# powerStage.net
KiCad netlist of a schematic drawn in EAGLE
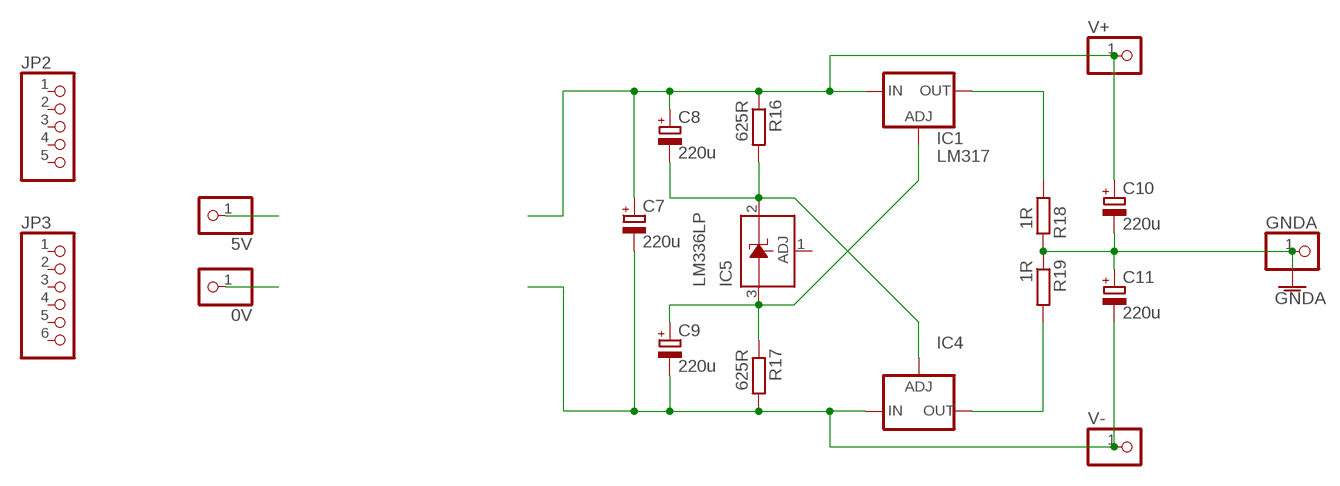
[diagram p0: schematic, sheet 1]

(export (version "E")
  (design (tool "Eeschema 10.0.6"))
  (components
    (comp (ref "0V")
      (value "PINHD-1X1")
      (footprint "eagle-import:1X01")
      (libsource (lib "eagle-import") (part "PINHD-1X1"))
    )
    (comp (ref "5V")
      (value "PINHD-1X1")
      (footprint "eagle-import:1X01")
      (libsource (lib "eagle-import") (part "PINHD-1X1"))
    )
    (comp (ref "C7")
      (value "220u")
      (footprint "eagle-import:E2-5")
      (libsource (lib "eagle-import") (part "CPOL-EUE2-5"))
    )
    (comp (ref "C8")
      (value "220u")
      (footprint "eagle-import:E2-5")
      (libsource (lib "eagle-import") (part "CPOL-EUE2-5"))
    )
    (comp (ref "C9")
      (value "220u")
      (footprint "eagle-import:E2-5")
      (libsource (lib "eagle-import") (part "CPOL-EUE2-5"))
    )
    (comp (ref "C10")
      (value "220u")
      (footprint "eagle-import:E2-5")
      (libsource (lib "eagle-import") (part "CPOL-EUE2-5"))
    )
    (comp (ref "C11")
      (value "220u")
      (footprint "eagle-import:E2-5")
      (libsource (lib "eagle-import") (part "CPOL-EUE2-5"))
    )
    (comp (ref "GNDA")
      (value "PINHD-1X1")
      (footprint "eagle-import:1X01")
      (libsource (lib "eagle-import") (part "PINHD-1X1"))
    )
    (comp (ref "IC1")
      (value "LM317")
      (footprint "eagle-import:TO220L1")
      (libsource (lib "eagle-import") (part "LM317?MB"))
    )
    (comp (ref "IC4")
      (value "LM337TL")
      (footprint "eagle-import:337TL")
      (libsource (lib "eagle-import") (part "LM337TL"))
    )
    (comp (ref "IC5")
      (value "LM336LP")
      (footprint "eagle-import:TO92")
      (libsource (lib "eagle-import") (part "LM336LP"))
    )
    (comp (ref "JP2")
      (value "PINHD-1X5")
      (footprint "eagle-import:1X05")
      (libsource (lib "eagle-import") (part "PINHD-1X5"))
    )
    (comp (ref "JP3")
      (value "PINHD-1X6")
      (footprint "eagle-import:1X06")
      (libsource (lib "eagle-import") (part "PINHD-1X6"))
    )
    (comp (ref "R16")
      (value "625R")
      (footprint "eagle-import:0207_7")
      (libsource (lib "eagle-import") (part "R-EU_0207/7"))
    )
    (comp (ref "R17")
      (value "625R")
      (footprint "eagle-import:0207_7")
      (libsource (lib "eagle-import") (part "R-EU_0207/7"))
    )
    (comp (ref "R18")
      (value "1R")
      (footprint "eagle-import:0207_7")
      (libsource (lib "eagle-import") (part "R-EU_0207/7"))
    )
    (comp (ref "R19")
      (value "1R")
      (footprint "eagle-import:0207_7")
      (libsource (lib "eagle-import") (part "R-EU_0207/7"))
    )
    (comp (ref "V+")
      (value "PINHD-1X1")
      (footprint "eagle-import:1X01")
      (libsource (lib "eagle-import") (part "PINHD-1X1"))
    )
    (comp (ref "V-")
      (value "PINHD-1X1")
      (footprint "eagle-import:1X01")
      (libsource (lib "eagle-import") (part "PINHD-1X1"))
    )
  )
  (nets
    (net (code "1") (name "GNDA") (class "Default")
      (node (ref "C10") (pin "-") (pinfunction "-_-") (pintype "passive"))
      (node (ref "C11") (pin "+") (pinfunction "+_+") (pintype "passive"))
      (node (ref "GNDA") (pin "1") (pinfunction "1_1") (pintype "passive"))
      (node (ref "R18") (pin "2") (pinfunction "2_2") (pintype "passive"))
      (node (ref "R19") (pin "1") (pinfunction "1_1") (pintype "passive"))
    )
    (net (code "2") (name "Net-(IC1-ADJ)") (class "Default")
      (node (ref "C9") (pin "+") (pinfunction "+_+") (pintype "passive"))
      (node (ref "IC1") (pin "1") (pinfunction "ADJ_1") (pintype "input"))
      (node (ref "IC5") (pin "3") (pinfunction "A_3") (pintype "input"))
      (node (ref "R17") (pin "1") (pinfunction "1_1") (pintype "passive"))
    )
    (net (code "3") (name "Net-(IC1-IN)") (class "Default")
      (node (ref "C10") (pin "+") (pinfunction "+_+") (pintype "passive"))
      (node (ref "C7") (pin "+") (pinfunction "+_+") (pintype "passive"))
      (node (ref "C8") (pin "+") (pinfunction "+_+") (pintype "passive"))
      (node (ref "IC1") (pin "3") (pinfunction "IN_3") (pintype "input"))
      (node (ref "R16") (pin "1") (pinfunction "1_1") (pintype "passive"))
      (node (ref "V+") (pin "1") (pinfunction "1_1") (pintype "passive"))
    )
    (net (code "4") (name "Net-(IC1-OUT)") (class "Default")
      (node (ref "IC1") (pin "2") (pinfunction "OUT_2") (pintype "passive"))
      (node (ref "R18") (pin "1") (pinfunction "1_1") (pintype "passive"))
    )
    (net (code "5") (name "Net-(IC4-ADJ)") (class "Default")
      (node (ref "C8") (pin "-") (pinfunction "-_-") (pintype "passive"))
      (node (ref "IC4") (pin "1") (pinfunction "ADJ_1") (pintype "input"))
      (node (ref "IC5") (pin "2") (pinfunction "C_2") (pintype "passive"))
      (node (ref "R16") (pin "2") (pinfunction "2_2") (pintype "passive"))
    )
    (net (code "6") (name "Net-(IC4-IN)") (class "Default")
      (node (ref "C11") (pin "-") (pinfunction "-_-") (pintype "passive"))
      (node (ref "C7") (pin "-") (pinfunction "-_-") (pintype "passive"))
      (node (ref "C9") (pin "-") (pinfunction "-_-") (pintype "passive"))
      (node (ref "IC4") (pin "2") (pinfunction "IN_2") (pintype "input"))
      (node (ref "R17") (pin "2") (pinfunction "2_2") (pintype "passive"))
      (node (ref "V-") (pin "1") (pinfunction "1_1") (pintype "passive"))
    )
    (net (code "7") (name "Net-(IC4-OUT)") (class "Default")
      (node (ref "IC4") (pin "3") (pinfunction "OUT_3") (pintype "passive"))
      (node (ref "R19") (pin "2") (pinfunction "2_2") (pintype "passive"))
    )
    (net (code "8") (name "unconnected-(0V-Pad1)") (class "Default")
      (node (ref "0V") (pin "1") (pinfunction "1_1") (pintype "passive"))
    )
    (net (code "9") (name "unconnected-(5V-Pad1)") (class "Default")
      (node (ref "5V") (pin "1") (pinfunction "1_1") (pintype "passive"))
    )
    (net (code "10") (name "unconnected-(IC5-ADJ-Pad1)") (class "Default")
      (node (ref "IC5") (pin "1") (pinfunction "ADJ_1") (pintype "input"))
    )
    (net (code "11") (name "unconnected-(JP2-Pad1)") (class "Default")
      (node (ref "JP2") (pin "1") (pinfunction "1_1") (pintype "passive"))
    )
    (net (code "12") (name "unconnected-(JP2-Pad2)") (class "Default")
      (node (ref "JP2") (pin "2") (pinfunction "2_2") (pintype "passive"))
    )
    (net (code "13") (name "unconnected-(JP2-Pad3)") (class "Default")
      (node (ref "JP2") (pin "3") (pinfunction "3_3") (pintype "passive"))
    )
    (net (code "14") (name "unconnected-(JP2-Pad4)") (class "Default")
      (node (ref "JP2") (pin "4") (pinfunction "4_4") (pintype "passive"))
    )
    (net (code "15") (name "unconnected-(JP2-Pad5)") (class "Default")
      (node (ref "JP2") (pin "5") (pinfunction "5_5") (pintype "passive"))
    )
    (net (code "16") (name "unconnected-(JP3-Pad1)") (class "Default")
      (node (ref "JP3") (pin "1") (pinfunction "1_1") (pintype "passive"))
    )
    (net (code "17") (name "unconnected-(JP3-Pad2)") (class "Default")
      (node (ref "JP3") (pin "2") (pinfunction "2_2") (pintype "passive"))
    )
    (net (code "18") (name "unconnected-(JP3-Pad3)") (class "Default")
      (node (ref "JP3") (pin "3") (pinfunction "3_3") (pintype "passive"))
    )
    (net (code "19") (name "unconnected-(JP3-Pad4)") (class "Default")
      (node (ref "JP3") (pin "4") (pinfunction "4_4") (pintype "passive"))
    )
    (net (code "20") (name "unconnected-(JP3-Pad5)") (class "Default")
      (node (ref "JP3") (pin "5") (pinfunction "5_5") (pintype "passive"))
    )
    (net (code "21") (name "unconnected-(JP3-Pad6)") (class "Default")
      (node (ref "JP3") (pin "6") (pinfunction "6_6") (pintype "passive"))
    )
  )
)
